# NSHID.net
KiCad netlist of a schematic drawn in Altium Designer
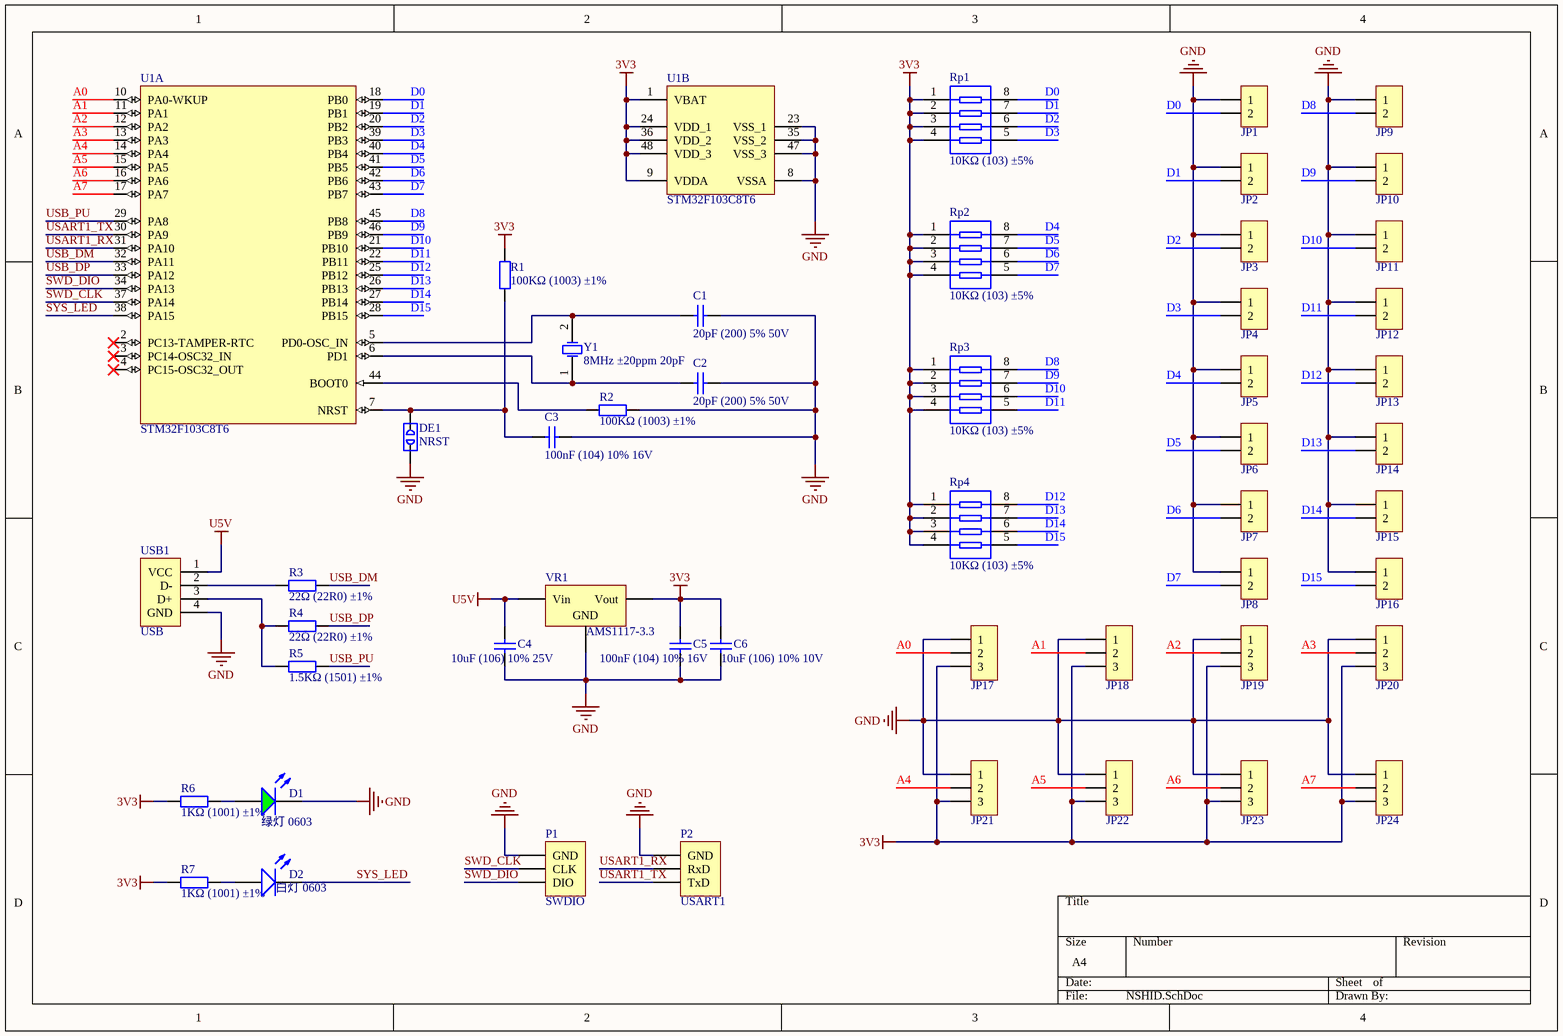
[diagram p0: NSHID.SchDoc]

(export (version "E")
  (design (tool "Eeschema 10.0.6"))
  (components
    (comp (ref "C1")
      (value "20pF (200) 5% 50V")
      (footprint "0402_C")
      (description "贴片电容")
      (libsource (lib "Miscellaneous Devices LC") (part "0402 20pF (200) 5% 50V"))
    )
    (comp (ref "C2")
      (value "20pF (200) 5% 50V")
      (footprint "0402_C")
      (description "贴片电容")
      (libsource (lib "Miscellaneous Devices LC") (part "0402 20pF (200) 5% 50V"))
    )
    (comp (ref "C3")
      (value "100nF (104) 10% 16V")
      (footprint "0402_C")
      (description "贴片电容")
      (libsource (lib "Miscellaneous Devices LC") (part "0402 100nF (104) 10% 16V"))
    )
    (comp (ref "C4")
      (value "10uF (106) 10% 25V")
      (footprint "0805_C")
      (description "贴片电容")
      (libsource (lib "Miscellaneous Devices LC") (part "0805 10uF (106) 10% 25V"))
    )
    (comp (ref "C5")
      (value "100nF (104) 10% 16V")
      (footprint "0402_C")
      (description "贴片电容")
      (libsource (lib "Miscellaneous Devices LC") (part "0402 100nF (104) 10% 16V"))
    )
    (comp (ref "C6")
      (value "10uF (106) 10% 10V")
      (footprint "0603_C")
      (description "贴片电容")
      (libsource (lib "Miscellaneous Devices LC") (part "0603 10uF (106) 10% 10V"))
    )
    (comp (ref "D1")
      (value "绿灯 0603")
      (footprint "0603_LED_S1")
      (description "发光二极管")
      (libsource (lib "Miscellaneous Devices LC") (part "0603 绿灯"))
    )
    (comp (ref "D2")
      (value "白灯 0603")
      (footprint "0603_LED_S1")
      (description "发光二极管")
      (libsource (lib "Miscellaneous Devices LC") (part "0603 白灯"))
    )
    (comp (ref "DE1")
      (value "NRST")
      (footprint "DEBUG_A")
      (description "调试断点焊盘")
      (fields (field (name "版权归属") "源创客"))
      (libsource (lib "15.1 - 未分类器件") (part "DEBUG"))
    )
    (comp (ref "JP1")
      (value "HDR-1X2")
      (footprint "XH2.54-LI-2P")
      (description "2P接插件")
      (fields (field (name "版权归属") "源创客"))
      (libsource (lib "4.5   - 接插件-脚距2.54") (part "Header 2"))
    )
    (comp (ref "JP2")
      (value "HDR-1X2")
      (footprint "XH2.54-LI-2P")
      (description "2P接插件")
      (fields (field (name "版权归属") "源创客"))
      (libsource (lib "4.5   - 接插件-脚距2.54") (part "Header 2"))
    )
    (comp (ref "JP3")
      (value "HDR-1X2")
      (footprint "XH2.54-LI-2P")
      (description "2P接插件")
      (fields (field (name "版权归属") "源创客"))
      (libsource (lib "4.5   - 接插件-脚距2.54") (part "Header 2"))
    )
    (comp (ref "JP4")
      (value "HDR-1X2")
      (footprint "XH2.54-LI-2P")
      (description "2P接插件")
      (fields (field (name "版权归属") "源创客"))
      (libsource (lib "4.5   - 接插件-脚距2.54") (part "Header 2"))
    )
    (comp (ref "JP5")
      (value "HDR-1X2")
      (footprint "XH2.54-LI-2P")
      (description "2P接插件")
      (fields (field (name "版权归属") "源创客"))
      (libsource (lib "4.5   - 接插件-脚距2.54") (part "Header 2"))
    )
    (comp (ref "JP6")
      (value "HDR-1X2")
      (footprint "XH2.54-LI-2P")
      (description "2P接插件")
      (fields (field (name "版权归属") "源创客"))
      (libsource (lib "4.5   - 接插件-脚距2.54") (part "Header 2"))
    )
    (comp (ref "JP7")
      (value "HDR-1X2")
      (footprint "XH2.54-LI-2P")
      (description "2P接插件")
      (fields (field (name "版权归属") "源创客"))
      (libsource (lib "4.5   - 接插件-脚距2.54") (part "Header 2"))
    )
    (comp (ref "JP8")
      (value "HDR-1X2")
      (footprint "XH2.54-LI-2P")
      (description "2P接插件")
      (fields (field (name "版权归属") "源创客"))
      (libsource (lib "4.5   - 接插件-脚距2.54") (part "Header 2"))
    )
    (comp (ref "JP9")
      (value "HDR-1X2")
      (footprint "XH2.54-LI-2P")
      (description "2P接插件")
      (fields (field (name "版权归属") "源创客"))
      (libsource (lib "4.5   - 接插件-脚距2.54") (part "Header 2"))
    )
    (comp (ref "JP10")
      (value "HDR-1X2")
      (footprint "XH2.54-LI-2P")
      (description "2P接插件")
      (fields (field (name "版权归属") "源创客"))
      (libsource (lib "4.5   - 接插件-脚距2.54") (part "Header 2"))
    )
    (comp (ref "JP11")
      (value "HDR-1X2")
      (footprint "XH2.54-LI-2P")
      (description "2P接插件")
      (fields (field (name "版权归属") "源创客"))
      (libsource (lib "4.5   - 接插件-脚距2.54") (part "Header 2"))
    )
    (comp (ref "JP12")
      (value "HDR-1X2")
      (footprint "XH2.54-LI-2P")
      (description "2P接插件")
      (fields (field (name "版权归属") "源创客"))
      (libsource (lib "4.5   - 接插件-脚距2.54") (part "Header 2"))
    )
    (comp (ref "JP13")
      (value "HDR-1X2")
      (footprint "XH2.54-LI-2P")
      (description "2P接插件")
      (fields (field (name "版权归属") "源创客"))
      (libsource (lib "4.5   - 接插件-脚距2.54") (part "Header 2"))
    )
    (comp (ref "JP14")
      (value "HDR-1X2")
      (footprint "XH2.54-LI-2P")
      (description "2P接插件")
      (fields (field (name "版权归属") "源创客"))
      (libsource (lib "4.5   - 接插件-脚距2.54") (part "Header 2"))
    )
    (comp (ref "JP15")
      (value "HDR-1X2")
      (footprint "XH2.54-LI-2P")
      (description "2P接插件")
      (fields (field (name "版权归属") "源创客"))
      (libsource (lib "4.5   - 接插件-脚距2.54") (part "Header 2"))
    )
    (comp (ref "JP16")
      (value "HDR-1X2")
      (footprint "XH2.54-LI-2P")
      (description "2P接插件")
      (fields (field (name "版权归属") "源创客"))
      (libsource (lib "4.5   - 接插件-脚距2.54") (part "Header 2"))
    )
    (comp (ref "JP17")
      (value "HDR-1X3")
      (footprint "XH2.54-LI-3P")
      (description "3P接插件")
      (fields (field (name "版权归属") "源创客"))
      (libsource (lib "4.5   - 接插件-脚距2.54") (part "Header 3"))
    )
    (comp (ref "JP18")
      (value "HDR-1X3")
      (footprint "XH2.54-LI-3P")
      (description "3P接插件")
      (fields (field (name "版权归属") "源创客"))
      (libsource (lib "4.5   - 接插件-脚距2.54") (part "Header 3"))
    )
    (comp (ref "JP19")
      (value "HDR-1X3")
      (footprint "XH2.54-LI-3P")
      (description "3P接插件")
      (fields (field (name "版权归属") "源创客"))
      (libsource (lib "4.5   - 接插件-脚距2.54") (part "Header 3"))
    )
    (comp (ref "JP20")
      (value "HDR-1X3")
      (footprint "XH2.54-LI-3P")
      (description "3P接插件")
      (fields (field (name "版权归属") "源创客"))
      (libsource (lib "4.5   - 接插件-脚距2.54") (part "Header 3"))
    )
    (comp (ref "JP21")
      (value "HDR-1X3")
      (footprint "XH2.54-LI-3P")
      (description "3P接插件")
      (fields (field (name "版权归属") "源创客"))
      (libsource (lib "4.5   - 接插件-脚距2.54") (part "Header 3"))
    )
    (comp (ref "JP22")
      (value "HDR-1X3")
      (footprint "XH2.54-LI-3P")
      (description "3P接插件")
      (fields (field (name "版权归属") "源创客"))
      (libsource (lib "4.5   - 接插件-脚距2.54") (part "Header 3"))
    )
    (comp (ref "JP23")
      (value "HDR-1X3")
      (footprint "XH2.54-LI-3P")
      (description "3P接插件")
      (fields (field (name "版权归属") "源创客"))
      (libsource (lib "4.5   - 接插件-脚距2.54") (part "Header 3"))
    )
    (comp (ref "JP24")
      (value "HDR-1X3")
      (footprint "XH2.54-LI-3P")
      (description "3P接插件")
      (fields (field (name "版权归属") "源创客"))
      (libsource (lib "4.5   - 接插件-脚距2.54") (part "Header 3"))
    )
    (comp (ref "P1")
      (value "SWDIO")
      (footprint "HDR1X3")
      (description "Header, 3-Pin")
      (fields (field (name "PUBLISHER") "Altium Limited"))
      (libsource (lib "Miscellaneous Connectors") (part "Header 3"))
    )
    (comp (ref "P2")
      (value "USART1")
      (footprint "HDR1X3")
      (description "Header, 3-Pin")
      (fields (field (name "PUBLISHER") "Altium Limited"))
      (libsource (lib "Miscellaneous Connectors") (part "Header 3"))
    )
    (comp (ref "R1")
      (value "100KΩ (1003) ±1%")
      (footprint "0402_R")
      (description "贴片电阻")
      (libsource (lib "") (part "0402 100KΩ (1003) 1%_1"))
    )
    (comp (ref "R2")
      (value "100KΩ (1003) ±1%")
      (footprint "0402_R")
      (description "贴片电阻")
      (libsource (lib "Miscellaneous Devices LC") (part "0402 100KΩ (1003) 1%"))
    )
    (comp (ref "R3")
      (value "22Ω (22R0) ±1%")
      (footprint "0402_R")
      (description "贴片电阻")
      (libsource (lib "Miscellaneous Devices LC") (part "0402 22Ω (22R0) 1%"))
    )
    (comp (ref "R4")
      (value "22Ω (22R0) ±1%")
      (footprint "0402_R")
      (description "贴片电阻")
      (libsource (lib "Miscellaneous Devices LC") (part "0402 22Ω (22R0) 1%"))
    )
    (comp (ref "R5")
      (value "1.5KΩ (1501) ±1%")
      (footprint "0402_R")
      (description "贴片电阻")
      (libsource (lib "Miscellaneous Devices LC") (part "0402 1.5KΩ (1501) 1%"))
    )
    (comp (ref "R6")
      (value "1KΩ (1001) ±1%")
      (footprint "0402_R")
      (description "贴片电阻")
      (libsource (lib "Miscellaneous Devices LC") (part "0402 1KΩ (1001) 1%"))
    )
    (comp (ref "R7")
      (value "1KΩ (1001) ±1%")
      (footprint "0402_R")
      (description "贴片电阻")
      (libsource (lib "") (part "0402 1KΩ (1001) 1%_1"))
    )
    (comp (ref "Rp1")
      (value "10KΩ (103) ±5%")
      (footprint "0402_Rx4")
      (description "贴片排阻")
      (libsource (lib "Miscellaneous Devices LC") (part "0402*4 10KΩ (103) 5%"))
    )
    (comp (ref "Rp2")
      (value "10KΩ (103) ±5%")
      (footprint "0402_Rx4")
      (description "贴片排阻")
      (libsource (lib "Miscellaneous Devices LC") (part "0402*4 10KΩ (103) 5%"))
    )
    (comp (ref "Rp3")
      (value "10KΩ (103) ±5%")
      (footprint "0402_Rx4")
      (description "贴片排阻")
      (libsource (lib "Miscellaneous Devices LC") (part "0402*4 10KΩ (103) 5%"))
    )
    (comp (ref "Rp4")
      (value "10KΩ (103) ±5%")
      (footprint "0402_Rx4")
      (description "贴片排阻")
      (libsource (lib "Miscellaneous Devices LC") (part "0402*4 10KΩ (103) 5%"))
    )
    (comp (ref "U1")
      (value "STM32F103C8T6")
      (footprint "LQFP-48_7x7x05P")
      (description "ARM")
      (libsource (lib "Miscellaneous Devices LC") (part "STM32F103C8T6"))
    )
    (comp (ref "USB1")
      (value "USB")
      (footprint "USB-B/S_A")
      (description "USB-B型母接口")
      (fields (field (name "版权归属") "源创客"))
      (libsource (lib "4.1   - 接口类") (part "USB-B/S"))
    )
    (comp (ref "VR1")
      (value "AMS1117-3.3")
      (footprint "SOT-223")
      (description "低压差线性稳压(LDO)")
      (libsource (lib "Miscellaneous Devices LC") (part "SOT-223 AMS1117-3.3"))
    )
    (comp (ref "Y1")
      (value "8MHz ±20ppm 20pF")
      (footprint "SMD-5032_2P")
      (description "贴片晶振")
      (libsource (lib "Miscellaneous Devices LC") (part "SMD-5032_2P 8MHz 20ppm 20pF"))
    )
  )
  (nets
    (net (code "1") (name "/A0") (class "Default")
      (node (ref "JP17") (pin "2") (pinfunction "2_2") (pintype "passive"))
      (node (ref "U1") (pin "10") (pinfunction "PA0-WKUP_10") (pintype "bidirectional"))
    )
    (net (code "2") (name "/A1") (class "Default")
      (node (ref "JP18") (pin "2") (pinfunction "2_2") (pintype "passive"))
      (node (ref "U1") (pin "11") (pinfunction "PA1_11") (pintype "bidirectional"))
    )
    (net (code "3") (name "/A2") (class "Default")
      (node (ref "JP19") (pin "2") (pinfunction "2_2") (pintype "passive"))
      (node (ref "U1") (pin "12") (pinfunction "PA2_12") (pintype "bidirectional"))
    )
    (net (code "4") (name "/A3") (class "Default")
      (node (ref "JP20") (pin "2") (pinfunction "2_2") (pintype "passive"))
      (node (ref "U1") (pin "13") (pinfunction "PA3_13") (pintype "bidirectional"))
    )
    (net (code "5") (name "/A4") (class "Default")
      (node (ref "JP21") (pin "2") (pinfunction "2_2") (pintype "passive"))
      (node (ref "U1") (pin "14") (pinfunction "PA4_14") (pintype "bidirectional"))
    )
    (net (code "6") (name "/A5") (class "Default")
      (node (ref "JP22") (pin "2") (pinfunction "2_2") (pintype "passive"))
      (node (ref "U1") (pin "15") (pinfunction "PA5_15") (pintype "bidirectional"))
    )
    (net (code "7") (name "/A6") (class "Default")
      (node (ref "JP23") (pin "2") (pinfunction "2_2") (pintype "passive"))
      (node (ref "U1") (pin "16") (pinfunction "PA6_16") (pintype "bidirectional"))
    )
    (net (code "8") (name "/A7") (class "Default")
      (node (ref "JP24") (pin "2") (pinfunction "2_2") (pintype "passive"))
      (node (ref "U1") (pin "17") (pinfunction "PA7_17") (pintype "bidirectional"))
    )
    (net (code "9") (name "/D0") (class "Default")
      (node (ref "JP1") (pin "2") (pinfunction "2_2") (pintype "passive"))
      (node (ref "Rp1") (pin "8") (pinfunction "8_8") (pintype "passive"))
      (node (ref "U1") (pin "18") (pinfunction "PB0_18") (pintype "bidirectional"))
    )
    (net (code "10") (name "/D1") (class "Default")
      (node (ref "JP2") (pin "2") (pinfunction "2_2") (pintype "passive"))
      (node (ref "Rp1") (pin "7") (pinfunction "7_7") (pintype "passive"))
      (node (ref "U1") (pin "19") (pinfunction "PB1_19") (pintype "bidirectional"))
    )
    (net (code "11") (name "/D2") (class "Default")
      (node (ref "JP3") (pin "2") (pinfunction "2_2") (pintype "passive"))
      (node (ref "Rp1") (pin "6") (pinfunction "6_6") (pintype "passive"))
      (node (ref "U1") (pin "20") (pinfunction "PB2_20") (pintype "bidirectional"))
    )
    (net (code "12") (name "/D3") (class "Default")
      (node (ref "JP4") (pin "2") (pinfunction "2_2") (pintype "passive"))
      (node (ref "Rp1") (pin "5") (pinfunction "5_5") (pintype "passive"))
      (node (ref "U1") (pin "39") (pinfunction "PB3_39") (pintype "bidirectional"))
    )
    (net (code "13") (name "/D4") (class "Default")
      (node (ref "JP5") (pin "2") (pinfunction "2_2") (pintype "passive"))
      (node (ref "Rp2") (pin "8") (pinfunction "8_8") (pintype "passive"))
      (node (ref "U1") (pin "40") (pinfunction "PB4_40") (pintype "bidirectional"))
    )
    (net (code "14") (name "/D5") (class "Default")
      (node (ref "JP6") (pin "2") (pinfunction "2_2") (pintype "passive"))
      (node (ref "Rp2") (pin "7") (pinfunction "7_7") (pintype "passive"))
      (node (ref "U1") (pin "41") (pinfunction "PB5_41") (pintype "bidirectional"))
    )
    (net (code "15") (name "/D6") (class "Default")
      (node (ref "JP7") (pin "2") (pinfunction "2_2") (pintype "passive"))
      (node (ref "Rp2") (pin "6") (pinfunction "6_6") (pintype "passive"))
      (node (ref "U1") (pin "42") (pinfunction "PB6_42") (pintype "bidirectional"))
    )
    (net (code "16") (name "/D7") (class "Default")
      (node (ref "JP8") (pin "2") (pinfunction "2_2") (pintype "passive"))
      (node (ref "Rp2") (pin "5") (pinfunction "5_5") (pintype "passive"))
      (node (ref "U1") (pin "43") (pinfunction "PB7_43") (pintype "bidirectional"))
    )
    (net (code "17") (name "/D8") (class "Default")
      (node (ref "JP9") (pin "2") (pinfunction "2_2") (pintype "passive"))
      (node (ref "Rp3") (pin "8") (pinfunction "8_8") (pintype "passive"))
      (node (ref "U1") (pin "45") (pinfunction "PB8_45") (pintype "bidirectional"))
    )
    (net (code "18") (name "/D9") (class "Default")
      (node (ref "JP10") (pin "2") (pinfunction "2_2") (pintype "passive"))
      (node (ref "Rp3") (pin "7") (pinfunction "7_7") (pintype "passive"))
      (node (ref "U1") (pin "46") (pinfunction "PB9_46") (pintype "bidirectional"))
    )
    (net (code "19") (name "/D10") (class "Default")
      (node (ref "JP11") (pin "2") (pinfunction "2_2") (pintype "passive"))
      (node (ref "Rp3") (pin "6") (pinfunction "6_6") (pintype "passive"))
      (node (ref "U1") (pin "21") (pinfunction "PB10_21") (pintype "bidirectional"))
    )
    (net (code "20") (name "/D11") (class "Default")
      (node (ref "JP12") (pin "2") (pinfunction "2_2") (pintype "passive"))
      (node (ref "Rp3") (pin "5") (pinfunction "5_5") (pintype "passive"))
      (node (ref "U1") (pin "22") (pinfunction "PB11_22") (pintype "bidirectional"))
    )
    (net (code "21") (name "/D12") (class "Default")
      (node (ref "JP13") (pin "2") (pinfunction "2_2") (pintype "passive"))
      (node (ref "Rp4") (pin "8") (pinfunction "8_8") (pintype "passive"))
      (node (ref "U1") (pin "25") (pinfunction "PB12_25") (pintype "bidirectional"))
    )
    (net (code "22") (name "/D13") (class "Default")
      (node (ref "JP14") (pin "2") (pinfunction "2_2") (pintype "passive"))
      (node (ref "Rp4") (pin "7") (pinfunction "7_7") (pintype "passive"))
      (node (ref "U1") (pin "26") (pinfunction "PB13_26") (pintype "bidirectional"))
    )
    (net (code "23") (name "/D14") (class "Default")
      (node (ref "JP15") (pin "2") (pinfunction "2_2") (pintype "passive"))
      (node (ref "Rp4") (pin "6") (pinfunction "6_6") (pintype "passive"))
      (node (ref "U1") (pin "27") (pinfunction "PB14_27") (pintype "bidirectional"))
    )
    (net (code "24") (name "/D15") (class "Default")
      (node (ref "JP16") (pin "2") (pinfunction "2_2") (pintype "passive"))
      (node (ref "Rp4") (pin "5") (pinfunction "5_5") (pintype "passive"))
      (node (ref "U1") (pin "28") (pinfunction "PB15_28") (pintype "bidirectional"))
    )
    (net (code "25") (name "/SWD_CLK") (class "Default")
      (node (ref "P1") (pin "2") (pinfunction "CLK_2") (pintype "passive"))
      (node (ref "U1") (pin "37") (pinfunction "PA14_37") (pintype "bidirectional"))
    )
    (net (code "26") (name "/SWD_DIO") (class "Default")
      (node (ref "P1") (pin "3") (pinfunction "DIO_3") (pintype "passive"))
      (node (ref "U1") (pin "34") (pinfunction "PA13_34") (pintype "bidirectional"))
    )
    (net (code "27") (name "/SYS_LED") (class "Default")
      (node (ref "D2") (pin "K") (pinfunction "K_K") (pintype "passive"))
      (node (ref "U1") (pin "38") (pinfunction "PA15_38") (pintype "bidirectional"))
    )
    (net (code "28") (name "/USART1_RX") (class "Default")
      (node (ref "P2") (pin "2") (pinfunction "CLK_2") (pintype "passive"))
      (node (ref "U1") (pin "31") (pinfunction "PA10_31") (pintype "bidirectional"))
    )
    (net (code "29") (name "/USART1_TX") (class "Default")
      (node (ref "P2") (pin "3") (pinfunction "DIO_3") (pintype "passive"))
      (node (ref "U1") (pin "30") (pinfunction "PA9_30") (pintype "bidirectional"))
    )
    (net (code "30") (name "/USB_DM") (class "Default")
      (node (ref "R3") (pin "2") (pinfunction "2_2") (pintype "passive"))
      (node (ref "U1") (pin "32") (pinfunction "PA11_32") (pintype "bidirectional"))
    )
    (net (code "31") (name "/USB_DP") (class "Default")
      (node (ref "R4") (pin "2") (pinfunction "2_2") (pintype "passive"))
      (node (ref "U1") (pin "33") (pinfunction "PA12_33") (pintype "bidirectional"))
    )
    (net (code "32") (name "/USB_PU") (class "Default")
      (node (ref "R5") (pin "2") (pinfunction "2_2") (pintype "passive"))
      (node (ref "U1") (pin "29") (pinfunction "PA8_29") (pintype "bidirectional"))
    )
    (net (code "33") (name "3V3") (class "Default")
      (node (ref "C5") (pin "2") (pinfunction "2_2") (pintype "passive"))
      (node (ref "C6") (pin "2") (pinfunction "2_2") (pintype "passive"))
      (node (ref "JP17") (pin "3") (pinfunction "3_3") (pintype "passive"))
      (node (ref "JP18") (pin "3") (pinfunction "3_3") (pintype "passive"))
      (node (ref "JP19") (pin "3") (pinfunction "3_3") (pintype "passive"))
      (node (ref "JP20") (pin "3") (pinfunction "3_3") (pintype "passive"))
      (node (ref "JP21") (pin "3") (pinfunction "3_3") (pintype "passive"))
      (node (ref "JP22") (pin "3") (pinfunction "3_3") (pintype "passive"))
      (node (ref "JP23") (pin "3") (pinfunction "3_3") (pintype "passive"))
      (node (ref "JP24") (pin "3") (pinfunction "3_3") (pintype "passive"))
      (node (ref "R1") (pin "2") (pinfunction "2_2") (pintype "passive"))
      (node (ref "R6") (pin "1") (pinfunction "1_1") (pintype "passive"))
      (node (ref "R7") (pin "2") (pinfunction "2_2") (pintype "passive"))
      (node (ref "Rp1") (pin "1") (pinfunction "1_1") (pintype "passive"))
      (node (ref "Rp1") (pin "2") (pinfunction "2_2") (pintype "passive"))
      (node (ref "Rp1") (pin "3") (pinfunction "3_3") (pintype "passive"))
      (node (ref "Rp1") (pin "4") (pinfunction "4_4") (pintype "passive"))
      (node (ref "Rp2") (pin "1") (pinfunction "1_1") (pintype "passive"))
      (node (ref "Rp2") (pin "2") (pinfunction "2_2") (pintype "passive"))
      (node (ref "Rp2") (pin "3") (pinfunction "3_3") (pintype "passive"))
      (node (ref "Rp2") (pin "4") (pinfunction "4_4") (pintype "passive"))
      (node (ref "Rp3") (pin "1") (pinfunction "1_1") (pintype "passive"))
      (node (ref "Rp3") (pin "2") (pinfunction "2_2") (pintype "passive"))
      (node (ref "Rp3") (pin "3") (pinfunction "3_3") (pintype "passive"))
      (node (ref "Rp3") (pin "4") (pinfunction "4_4") (pintype "passive"))
      (node (ref "Rp4") (pin "1") (pinfunction "1_1") (pintype "passive"))
      (node (ref "Rp4") (pin "2") (pinfunction "2_2") (pintype "passive"))
      (node (ref "Rp4") (pin "3") (pinfunction "3_3") (pintype "passive"))
      (node (ref "Rp4") (pin "4") (pinfunction "4_4") (pintype "passive"))
      (node (ref "U1") (pin "1") (pinfunction "VBAT_1") (pintype "power_in"))
      (node (ref "U1") (pin "24") (pinfunction "VDD_1_24") (pintype "power_in"))
      (node (ref "U1") (pin "36") (pinfunction "VDD_2_36") (pintype "power_in"))
      (node (ref "U1") (pin "48") (pinfunction "VDD_3_48") (pintype "power_in"))
      (node (ref "U1") (pin "9") (pinfunction "VDDA_9") (pintype "power_in"))
      (node (ref "VR1") (pin "2") (pinfunction "Vout_2") (pintype "passive"))
    )
    (net (code "34") (name "GND") (class "Default")
      (node (ref "C1") (pin "2") (pinfunction "2_2") (pintype "passive"))
      (node (ref "C2") (pin "2") (pinfunction "2_2") (pintype "passive"))
      (node (ref "C3") (pin "1") (pinfunction "1_1") (pintype "passive"))
      (node (ref "C4") (pin "1") (pinfunction "1_1") (pintype "passive"))
      (node (ref "C5") (pin "1") (pinfunction "1_1") (pintype "passive"))
      (node (ref "C6") (pin "1") (pinfunction "1_1") (pintype "passive"))
      (node (ref "D1") (pin "K") (pinfunction "K_K") (pintype "passive"))
      (node (ref "DE1") (pin "2") (pinfunction "2_2") (pintype "passive"))
      (node (ref "JP1") (pin "1") (pinfunction "1_1") (pintype "passive"))
      (node (ref "JP10") (pin "1") (pinfunction "1_1") (pintype "passive"))
      (node (ref "JP11") (pin "1") (pinfunction "1_1") (pintype "passive"))
      (node (ref "JP12") (pin "1") (pinfunction "1_1") (pintype "passive"))
      (node (ref "JP13") (pin "1") (pinfunction "1_1") (pintype "passive"))
      (node (ref "JP14") (pin "1") (pinfunction "1_1") (pintype "passive"))
      (node (ref "JP15") (pin "1") (pinfunction "1_1") (pintype "passive"))
      (node (ref "JP16") (pin "1") (pinfunction "1_1") (pintype "passive"))
      (node (ref "JP17") (pin "1") (pinfunction "1_1") (pintype "passive"))
      (node (ref "JP18") (pin "1") (pinfunction "1_1") (pintype "passive"))
      (node (ref "JP19") (pin "1") (pinfunction "1_1") (pintype "passive"))
      (node (ref "JP2") (pin "1") (pinfunction "1_1") (pintype "passive"))
      (node (ref "JP20") (pin "1") (pinfunction "1_1") (pintype "passive"))
      (node (ref "JP21") (pin "1") (pinfunction "1_1") (pintype "passive"))
      (node (ref "JP22") (pin "1") (pinfunction "1_1") (pintype "passive"))
      (node (ref "JP23") (pin "1") (pinfunction "1_1") (pintype "passive"))
      (node (ref "JP24") (pin "1") (pinfunction "1_1") (pintype "passive"))
      (node (ref "JP3") (pin "1") (pinfunction "1_1") (pintype "passive"))
      (node (ref "JP4") (pin "1") (pinfunction "1_1") (pintype "passive"))
      (node (ref "JP5") (pin "1") (pinfunction "1_1") (pintype "passive"))
      (node (ref "JP6") (pin "1") (pinfunction "1_1") (pintype "passive"))
      (node (ref "JP7") (pin "1") (pinfunction "1_1") (pintype "passive"))
      (node (ref "JP8") (pin "1") (pinfunction "1_1") (pintype "passive"))
      (node (ref "JP9") (pin "1") (pinfunction "1_1") (pintype "passive"))
      (node (ref "P1") (pin "1") (pinfunction "GND_1") (pintype "passive"))
      (node (ref "P2") (pin "1") (pinfunction "GND_1") (pintype "passive"))
      (node (ref "R2") (pin "2") (pinfunction "2_2") (pintype "passive"))
      (node (ref "U1") (pin "23") (pinfunction "VSS_1_23") (pintype "power_in"))
      (node (ref "U1") (pin "35") (pinfunction "VSS_2_35") (pintype "power_in"))
      (node (ref "U1") (pin "47") (pinfunction "VSS_3_47") (pintype "power_in"))
      (node (ref "U1") (pin "8") (pinfunction "VSSA_8") (pintype "power_in"))
      (node (ref "USB1") (pin "4") (pinfunction "GND_4") (pintype "passive"))
      (node (ref "VR1") (pin "1") (pinfunction "GND_1") (pintype "passive"))
    )
    (net (code "35") (name "Net-(D1-PadA)") (class "Default")
      (node (ref "D1") (pin "A") (pinfunction "A_A") (pintype "passive"))
      (node (ref "R6") (pin "2") (pinfunction "2_2") (pintype "passive"))
    )
    (net (code "36") (name "Net-(D2-PadA)") (class "Default")
      (node (ref "D2") (pin "A") (pinfunction "A_A") (pintype "passive"))
      (node (ref "R7") (pin "1") (pinfunction "1_1") (pintype "passive"))
    )
    (net (code "37") (name "Net-(U1A-BOOT0)") (class "Default")
      (node (ref "R2") (pin "1") (pinfunction "1_1") (pintype "passive"))
      (node (ref "U1") (pin "44") (pinfunction "BOOT0_44") (pintype "input"))
    )
    (net (code "38") (name "Net-(U1A-NRST)") (class "Default")
      (node (ref "C3") (pin "2") (pinfunction "2_2") (pintype "passive"))
      (node (ref "DE1") (pin "1") (pinfunction "1_1") (pintype "passive"))
      (node (ref "R1") (pin "1") (pinfunction "1_1") (pintype "passive"))
      (node (ref "U1") (pin "7") (pinfunction "NRST_7") (pintype "bidirectional"))
    )
    (net (code "39") (name "Net-(U1A-PD0-OSC_IN)") (class "Default")
      (node (ref "C1") (pin "1") (pinfunction "1_1") (pintype "passive"))
      (node (ref "U1") (pin "5") (pinfunction "PD0-OSC_IN_5") (pintype "bidirectional"))
      (node (ref "Y1") (pin "2") (pinfunction "OSC2_2") (pintype "passive"))
    )
    (net (code "40") (name "Net-(U1A-PD1)") (class "Default")
      (node (ref "C2") (pin "1") (pinfunction "1_1") (pintype "passive"))
      (node (ref "U1") (pin "6") (pinfunction "PD1_6") (pintype "bidirectional"))
      (node (ref "Y1") (pin "1") (pinfunction "OSC1_1") (pintype "passive"))
    )
    (net (code "41") (name "Net-(USB1-D+)") (class "Default")
      (node (ref "R4") (pin "1") (pinfunction "1_1") (pintype "passive"))
      (node (ref "R5") (pin "1") (pinfunction "1_1") (pintype "passive"))
      (node (ref "USB1") (pin "3") (pinfunction "D+_3") (pintype "passive"))
    )
    (net (code "42") (name "Net-(USB1-D-)") (class "Default")
      (node (ref "R3") (pin "1") (pinfunction "1_1") (pintype "passive"))
      (node (ref "USB1") (pin "2") (pinfunction "D-_2") (pintype "passive"))
    )
    (net (code "43") (name "U5V") (class "Default")
      (node (ref "C4") (pin "2") (pinfunction "2_2") (pintype "passive"))
      (node (ref "USB1") (pin "1") (pinfunction "VCC_1") (pintype "passive"))
      (node (ref "VR1") (pin "3") (pinfunction "Vin_3") (pintype "passive"))
    )
    (net (code "44") (name "unconnected-(U1A-PC13-TAMPER-RTC-Pad2)") (class "Default")
      (node (ref "U1") (pin "2") (pinfunction "PC13-TAMPER-RTC_2") (pintype "bidirectional+no_connect"))
    )
    (net (code "45") (name "unconnected-(U1A-PC14-OSC32_IN-Pad3)") (class "Default")
      (node (ref "U1") (pin "3") (pinfunction "PC14-OSC32_IN_3") (pintype "bidirectional+no_connect"))
    )
    (net (code "46") (name "unconnected-(U1A-PC15-OSC32_OUT-Pad4)") (class "Default")
      (node (ref "U1") (pin "4") (pinfunction "PC15-OSC32_OUT_4") (pintype "bidirectional+no_connect"))
    )
  )
)
